# KN-CON_LCD.net
KiCad netlist of a schematic drawn in EAGLE
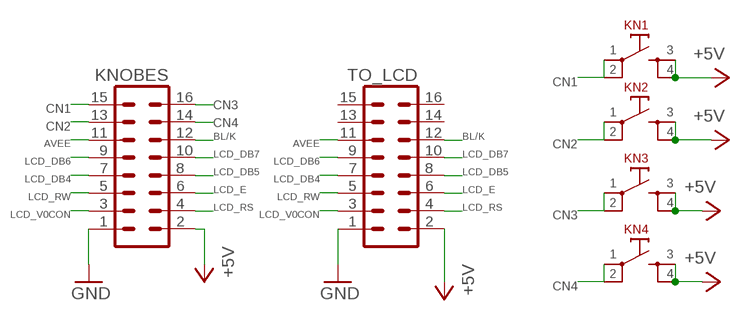
[diagram p0: schematic, sheet 1]

(export (version "E")
  (design (tool "Eeschema 10.0.6"))
  (components
    (comp (ref "KN1")
      (value "LZQ-KN")
      (footprint "eagle-import:LZQ-KN")
      (libsource (lib "eagle-import") (part "LZQ-KN"))
    )
    (comp (ref "KN2")
      (value "LZQ-KN")
      (footprint "eagle-import:LZQ-KN")
      (libsource (lib "eagle-import") (part "LZQ-KN"))
    )
    (comp (ref "KN3")
      (value "LZQ-KN")
      (footprint "eagle-import:LZQ-KN")
      (libsource (lib "eagle-import") (part "LZQ-KN"))
    )
    (comp (ref "KN4")
      (value "LZQ-KN")
      (footprint "eagle-import:LZQ-KN")
      (libsource (lib "eagle-import") (part "LZQ-KN"))
    )
    (comp (ref "KNOBES")
      (value "ML16")
      (footprint "eagle-import:ML16")
      (fields (field (name "OC_FARNELL") "unknown") (field (name "OC_NEWARK") "unknown"))
      (libsource (lib "eagle-import") (part "ML16"))
    )
    (comp (ref "TO_LCD")
      (value "ML16")
      (footprint "eagle-import:ML16")
      (fields (field (name "OC_FARNELL") "unknown") (field (name "OC_NEWARK") "unknown"))
      (libsource (lib "eagle-import") (part "ML16"))
    )
  )
  (nets
    (net (code "1") (name "+5V") (class "Default")
      (node (ref "KN1") (pin "3") (pinfunction "3_3") (pintype "bidirectional"))
      (node (ref "KN1") (pin "4") (pinfunction "4_4") (pintype "bidirectional"))
      (node (ref "KN2") (pin "3") (pinfunction "3_3") (pintype "bidirectional"))
      (node (ref "KN2") (pin "4") (pinfunction "4_4") (pintype "bidirectional"))
      (node (ref "KN3") (pin "3") (pinfunction "3_3") (pintype "bidirectional"))
      (node (ref "KN3") (pin "4") (pinfunction "4_4") (pintype "bidirectional"))
      (node (ref "KN4") (pin "3") (pinfunction "3_3") (pintype "bidirectional"))
      (node (ref "KN4") (pin "4") (pinfunction "4_4") (pintype "bidirectional"))
      (node (ref "KNOBES") (pin "2") (pinfunction "2_2") (pintype "passive"))
      (node (ref "TO_LCD") (pin "2") (pinfunction "2_2") (pintype "passive"))
    )
    (net (code "2") (name "/AVEE") (class "Default")
      (node (ref "KNOBES") (pin "11") (pinfunction "11_11") (pintype "passive"))
      (node (ref "TO_LCD") (pin "11") (pinfunction "11_11") (pintype "passive"))
    )
    (net (code "3") (name "/BL{slash}K") (class "Default")
      (node (ref "KNOBES") (pin "12") (pinfunction "12_12") (pintype "passive"))
      (node (ref "TO_LCD") (pin "12") (pinfunction "12_12") (pintype "passive"))
    )
    (net (code "4") (name "/CN1") (class "Default")
      (node (ref "KN1") (pin "1") (pinfunction "1_1") (pintype "bidirectional"))
      (node (ref "KN1") (pin "2") (pinfunction "2_2") (pintype "bidirectional"))
      (node (ref "KNOBES") (pin "15") (pinfunction "15_15") (pintype "passive"))
    )
    (net (code "5") (name "/CN2") (class "Default")
      (node (ref "KN2") (pin "1") (pinfunction "1_1") (pintype "bidirectional"))
      (node (ref "KN2") (pin "2") (pinfunction "2_2") (pintype "bidirectional"))
      (node (ref "KNOBES") (pin "13") (pinfunction "13_13") (pintype "passive"))
    )
    (net (code "6") (name "/CN3") (class "Default")
      (node (ref "KN3") (pin "1") (pinfunction "1_1") (pintype "bidirectional"))
      (node (ref "KN3") (pin "2") (pinfunction "2_2") (pintype "bidirectional"))
      (node (ref "KNOBES") (pin "16") (pinfunction "16_16") (pintype "passive"))
    )
    (net (code "7") (name "/CN4") (class "Default")
      (node (ref "KN4") (pin "1") (pinfunction "1_1") (pintype "bidirectional"))
      (node (ref "KN4") (pin "2") (pinfunction "2_2") (pintype "bidirectional"))
      (node (ref "KNOBES") (pin "14") (pinfunction "14_14") (pintype "passive"))
    )
    (net (code "8") (name "/LCD_DB4") (class "Default")
      (node (ref "KNOBES") (pin "7") (pinfunction "7_7") (pintype "passive"))
      (node (ref "TO_LCD") (pin "7") (pinfunction "7_7") (pintype "passive"))
    )
    (net (code "9") (name "/LCD_DB5") (class "Default")
      (node (ref "KNOBES") (pin "8") (pinfunction "8_8") (pintype "passive"))
      (node (ref "TO_LCD") (pin "8") (pinfunction "8_8") (pintype "passive"))
    )
    (net (code "10") (name "/LCD_DB6") (class "Default")
      (node (ref "KNOBES") (pin "9") (pinfunction "9_9") (pintype "passive"))
      (node (ref "TO_LCD") (pin "9") (pinfunction "9_9") (pintype "passive"))
    )
    (net (code "11") (name "/LCD_DB7") (class "Default")
      (node (ref "KNOBES") (pin "10") (pinfunction "10_10") (pintype "passive"))
      (node (ref "TO_LCD") (pin "10") (pinfunction "10_10") (pintype "passive"))
    )
    (net (code "12") (name "/LCD_E") (class "Default")
      (node (ref "KNOBES") (pin "6") (pinfunction "6_6") (pintype "passive"))
      (node (ref "TO_LCD") (pin "6") (pinfunction "6_6") (pintype "passive"))
    )
    (net (code "13") (name "/LCD_RS") (class "Default")
      (node (ref "KNOBES") (pin "4") (pinfunction "4_4") (pintype "passive"))
      (node (ref "TO_LCD") (pin "4") (pinfunction "4_4") (pintype "passive"))
    )
    (net (code "14") (name "/LCD_RW") (class "Default")
      (node (ref "KNOBES") (pin "5") (pinfunction "5_5") (pintype "passive"))
      (node (ref "TO_LCD") (pin "5") (pinfunction "5_5") (pintype "passive"))
    )
    (net (code "15") (name "/LCD_V0CON") (class "Default")
      (node (ref "KNOBES") (pin "3") (pinfunction "3_3") (pintype "passive"))
      (node (ref "TO_LCD") (pin "3") (pinfunction "3_3") (pintype "passive"))
    )
    (net (code "16") (name "GND") (class "Default")
      (node (ref "KNOBES") (pin "1") (pinfunction "1_1") (pintype "passive"))
      (node (ref "TO_LCD") (pin "1") (pinfunction "1_1") (pintype "passive"))
    )
    (net (code "17") (name "unconnected-(TO_LCD-Pad13)") (class "Default")
      (node (ref "TO_LCD") (pin "13") (pinfunction "13_13") (pintype "passive"))
    )
    (net (code "18") (name "unconnected-(TO_LCD-Pad14)") (class "Default")
      (node (ref "TO_LCD") (pin "14") (pinfunction "14_14") (pintype "passive"))
    )
    (net (code "19") (name "unconnected-(TO_LCD-Pad15)") (class "Default")
      (node (ref "TO_LCD") (pin "15") (pinfunction "15_15") (pintype "passive"))
    )
    (net (code "20") (name "unconnected-(TO_LCD-Pad16)") (class "Default")
      (node (ref "TO_LCD") (pin "16") (pinfunction "16_16") (pintype "passive"))
    )
  )
)
